# controller9.net
KiCad netlist of a schematic drawn in EAGLE
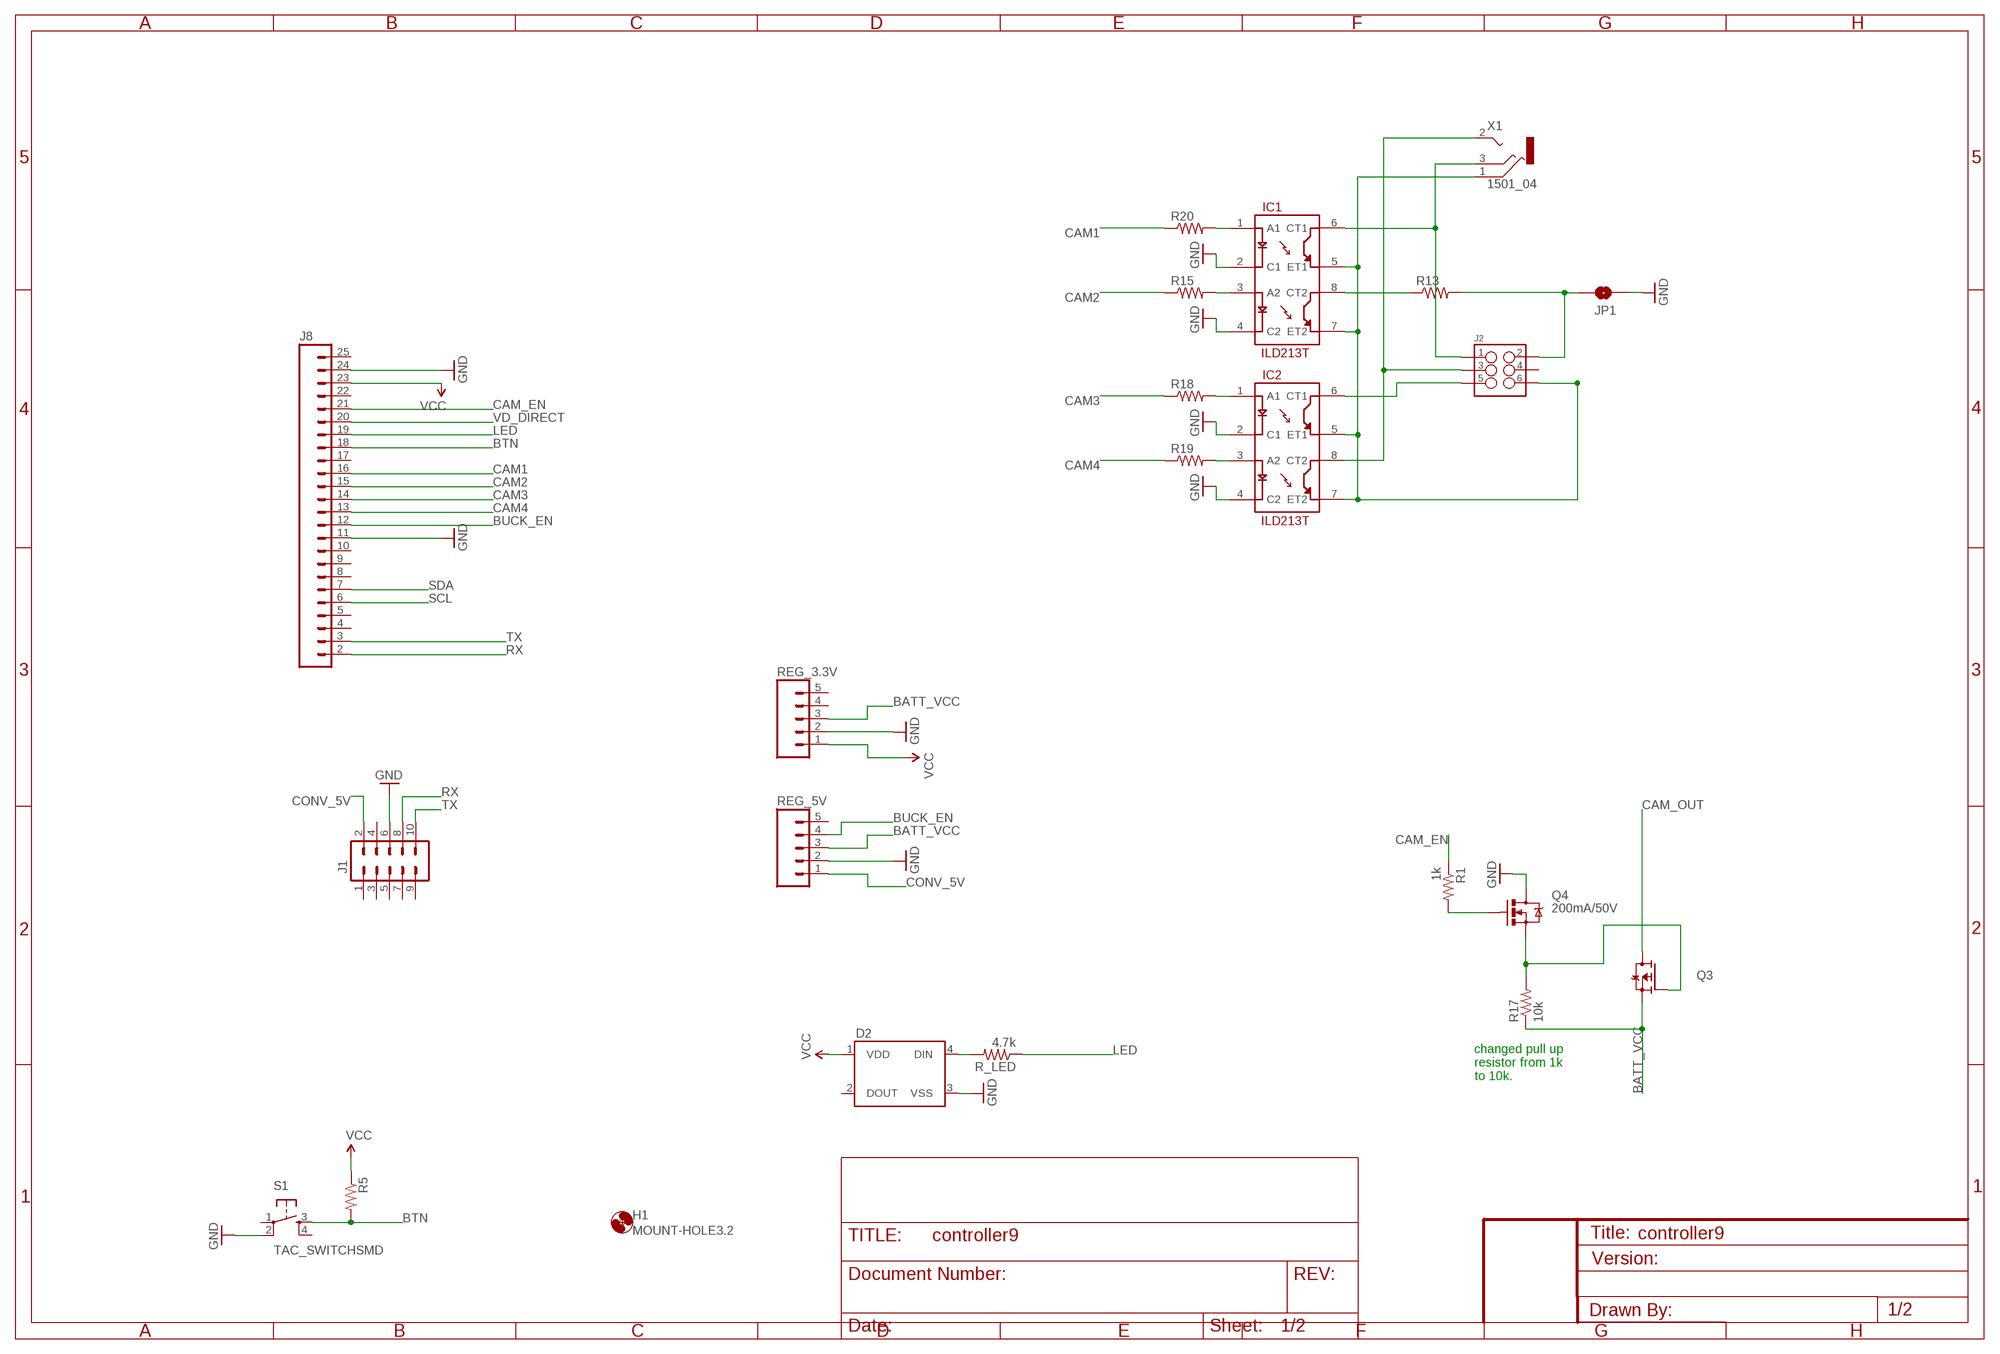
[diagram p0: schematic, sheet 1]
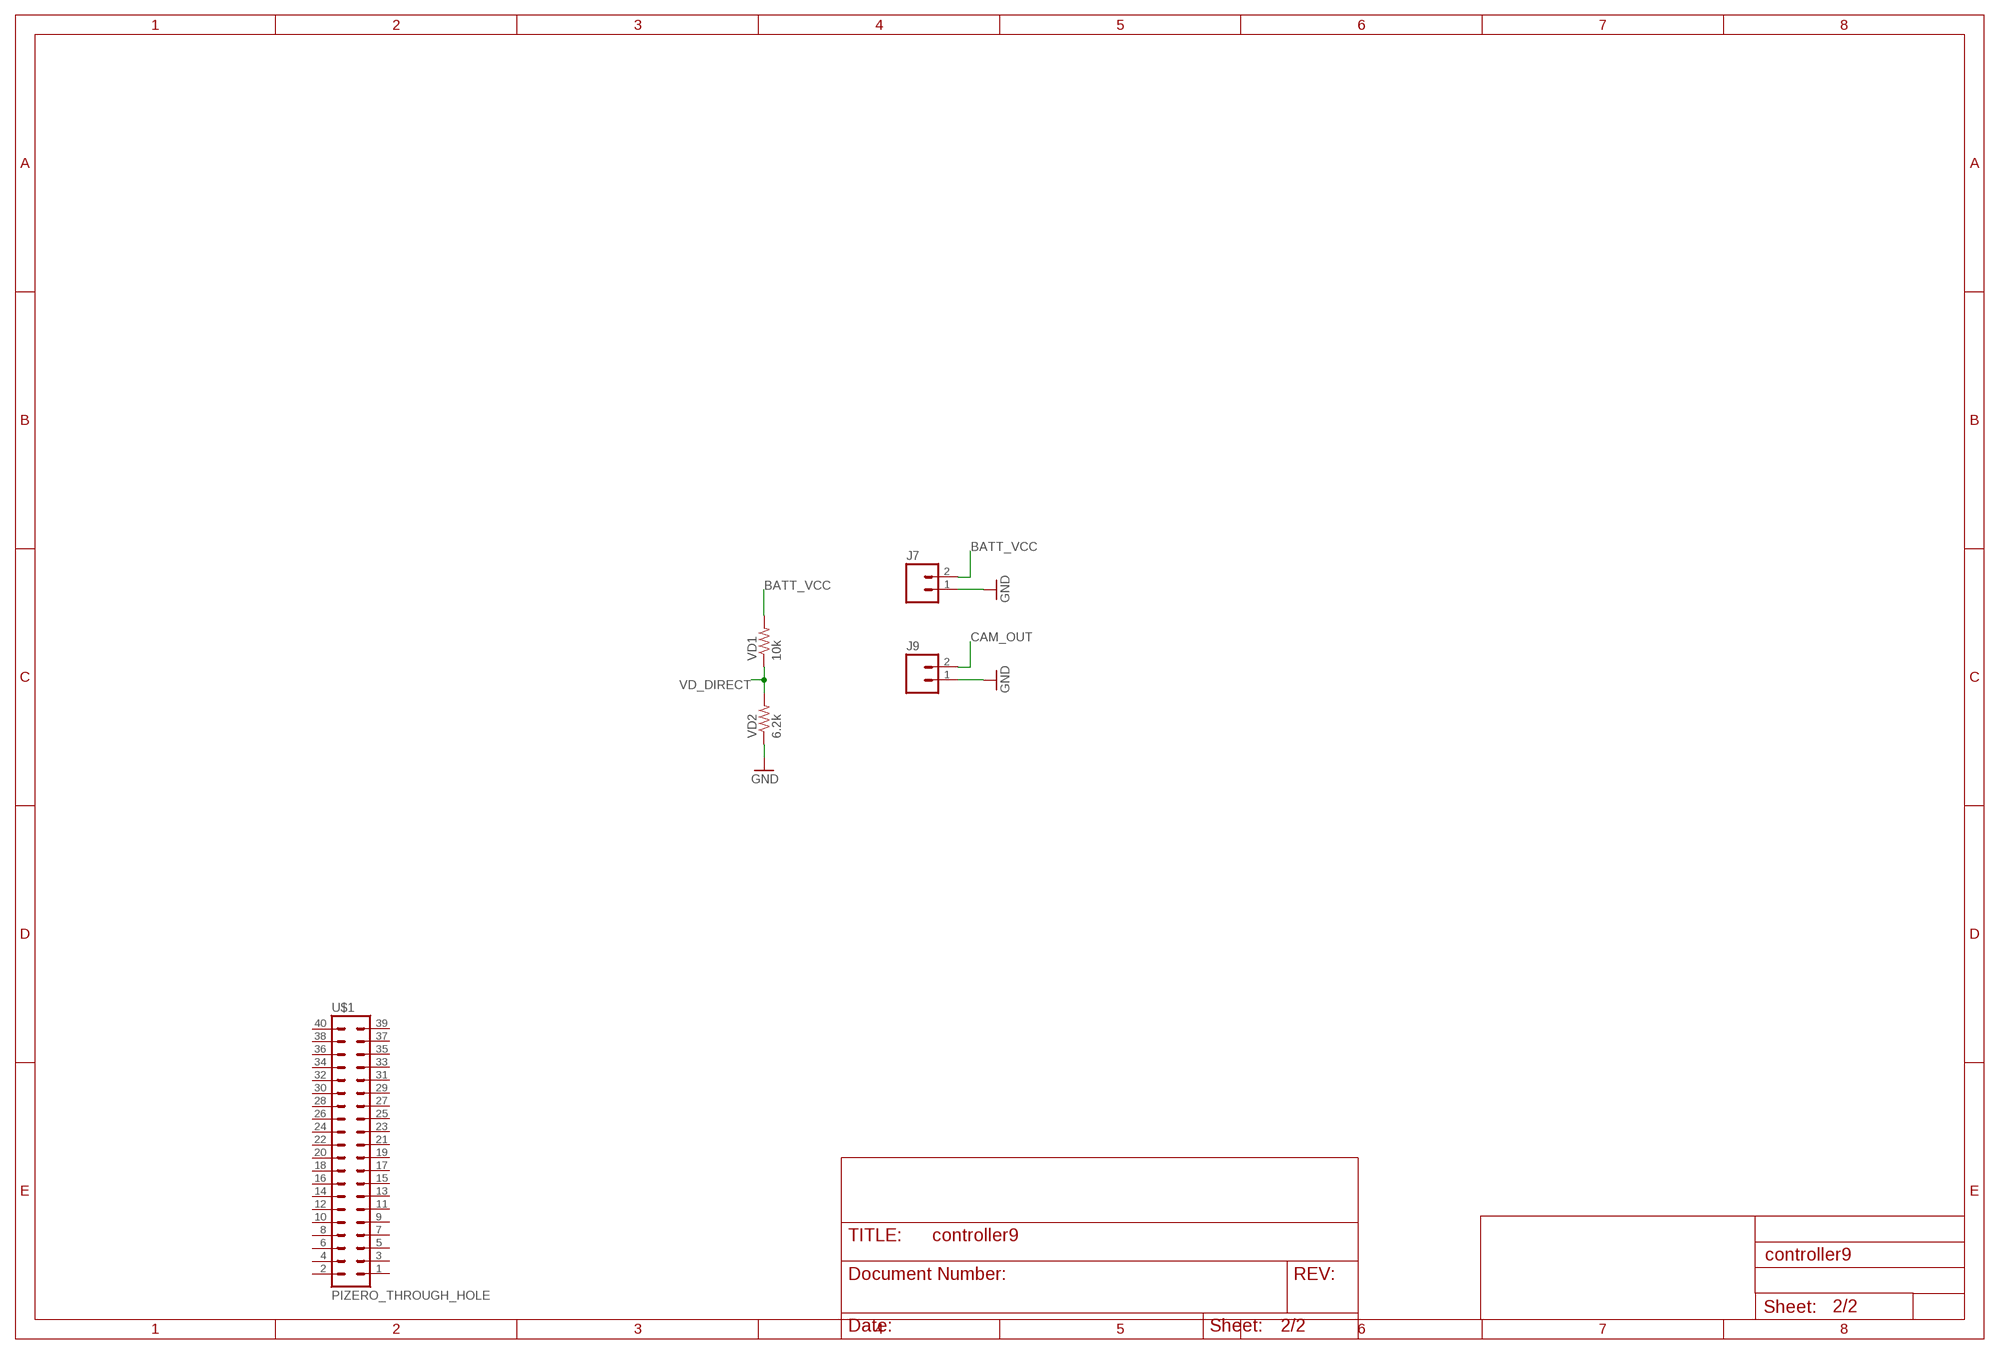
[diagram p1: schematic, sheet 2]

(export (version "E")
  (design (tool "Eeschema 10.0.6"))
  (components
    (comp (ref "J7")
      (value "M02LOCK")
      (footprint "eagle-import:1X02_LOCK")
      (libsource (lib "eagle-import") (part "M02LOCK"))
    )
    (comp (ref "J9")
      (value "M02LOCK")
      (footprint "eagle-import:1X02_LOCK")
      (libsource (lib "eagle-import") (part "M02LOCK"))
    )
    (comp (ref "U$1")
      (value "PIZERO_THROUGH_HOLE")
      (footprint "eagle-import:PIZERO_THOUGH_HOLE")
      (libsource (lib "eagle-import") (part "PIZERO_THROUGH_HOLE"))
    )
    (comp (ref "VD1")
      (value "10k")
      (footprint "eagle-import:0805")
      (libsource (lib "eagle-import") (part "RESISTOR0805-RES"))
    )
    (comp (ref "VD2")
      (value "6.2k")
      (footprint "eagle-import:0805")
      (libsource (lib "eagle-import") (part "RESISTOR0805-RES"))
    )
    (comp (ref "D2")
      (value "WS2812B")
      (footprint "eagle-import:WS2812B")
      (libsource (lib "eagle-import") (part "WS2812B"))
    )
    (comp (ref "H1")
      (value "MOUNT-HOLE3.2")
      (footprint "eagle-import:3,2")
      (libsource (lib "eagle-import") (part "MOUNT-HOLE3.2"))
    )
    (comp (ref "IC1")
      (value "ILD213T")
      (footprint "eagle-import:SO08")
      (libsource (lib "eagle-import") (part "ILD213T"))
    )
    (comp (ref "IC2")
      (value "ILD213T")
      (footprint "eagle-import:SO08")
      (libsource (lib "eagle-import") (part "ILD213T"))
    )
    (comp (ref "J1")
      (value "M05X2PTH")
      (footprint "eagle-import:AVR_ICSP")
      (libsource (lib "eagle-import") (part "M05X2PTH"))
    )
    (comp (ref "J2")
      (value "M03X2FEMALE")
      (footprint "eagle-import:2X3")
      (libsource (lib "eagle-import") (part "M03X2FEMALE"))
    )
    (comp (ref "J8")
      (value "M24LOCK")
      (footprint "eagle-import:1X24_LOCK")
      (libsource (lib "eagle-import") (part "M24LOCK"))
    )
    (comp (ref "JP1")
      (value "JUMPER-PAD-2-NOYES_SILK")
      (footprint "eagle-import:PAD-JUMPER-2-NO_YES_SILK")
      (libsource (lib "eagle-import") (part "JUMPER-PAD-2-NOYES_SILK"))
    )
    (comp (ref "Q3")
      (value "FDD4141TO252")
      (footprint "eagle-import:TO252")
      (libsource (lib "eagle-import") (part "FDD4141TO252"))
    )
    (comp (ref "Q4")
      (value "200mA/50V")
      (footprint "eagle-import:SOT23-3")
      (libsource (lib "eagle-import") (part "MOSFET-NCHANNELBSS138"))
    )
    (comp (ref "R1")
      (value "1k")
      (footprint "eagle-import:0805")
      (libsource (lib "eagle-import") (part "SparkFun-Resistors_RESISTOR0805-RES"))
    )
    (comp (ref "R5")
      (value "RESISTOR0805-RES")
      (footprint "eagle-import:0805")
      (libsource (lib "eagle-import") (part "RESISTOR0805-RES"))
    )
    (comp (ref "R13")
      (value "RESISTOR0805-RES")
      (footprint "eagle-import:0805")
      (libsource (lib "eagle-import") (part "RESISTOR0805-RES"))
    )
    (comp (ref "R15")
      (value "RESISTOR0805-RES")
      (footprint "eagle-import:0805")
      (libsource (lib "eagle-import") (part "RESISTOR0805-RES"))
    )
    (comp (ref "R17")
      (value "10k")
      (footprint "eagle-import:0805")
      (libsource (lib "eagle-import") (part "SparkFun-Resistors_RESISTOR0805-RES"))
    )
    (comp (ref "R18")
      (value "RESISTOR0805-RES")
      (footprint "eagle-import:0805")
      (libsource (lib "eagle-import") (part "RESISTOR0805-RES"))
    )
    (comp (ref "R19")
      (value "RESISTOR0805-RES")
      (footprint "eagle-import:0805")
      (libsource (lib "eagle-import") (part "RESISTOR0805-RES"))
    )
    (comp (ref "R20")
      (value "RESISTOR0805-RES")
      (footprint "eagle-import:0805")
      (libsource (lib "eagle-import") (part "RESISTOR0805-RES"))
    )
    (comp (ref "REG_3.3V")
      (value "M05LOCK")
      (footprint "eagle-import:1X05_LOCK")
      (libsource (lib "eagle-import") (part "M05LOCK"))
    )
    (comp (ref "REG_5V")
      (value "M05LOCK")
      (footprint "eagle-import:1X05_LOCK")
      (libsource (lib "eagle-import") (part "M05LOCK"))
    )
    (comp (ref "R_LED")
      (value "4.7k")
      (footprint "eagle-import:0805")
      (libsource (lib "eagle-import") (part "SparkFun-Resistors_RESISTOR0805-RES"))
    )
    (comp (ref "S1")
      (value "TAC_SWITCHSMD")
      (footprint "eagle-import:TACTILE-PTH")
      (libsource (lib "eagle-import") (part "TAC_SWITCHPTH"))
    )
    (comp (ref "X1")
      (value "1501_04")
      (footprint "eagle-import:1501_05")
      (libsource (lib "eagle-import") (part "1501_04"))
    )
  )
  (nets
    (net (code "1") (name "BATT_VCC") (class "Default")
      (node (ref "J7") (pin "2") (pinfunction "2_2") (pintype "passive"))
      (node (ref "Q3") (pin "2") (pinfunction "S_2") (pintype "passive"))
      (node (ref "R17") (pin "1") (pinfunction "1_1") (pintype "passive"))
      (node (ref "REG_3.3V") (pin "3") (pinfunction "3_3") (pintype "passive"))
      (node (ref "REG_5V") (pin "3") (pinfunction "3_3") (pintype "passive"))
      (node (ref "VD1") (pin "2") (pinfunction "2_2") (pintype "passive"))
    )
    (net (code "2") (name "BTN") (class "Default")
      (node (ref "J8") (pin "18") (pinfunction "18_18") (pintype "passive"))
      (node (ref "R5") (pin "2") (pinfunction "2_2") (pintype "passive"))
      (node (ref "S1") (pin "3") (pinfunction "3_3") (pintype "passive"))
    )
    (net (code "3") (name "BUCK_EN") (class "Default")
      (node (ref "J8") (pin "12") (pinfunction "12_12") (pintype "passive"))
      (node (ref "REG_5V") (pin "4") (pinfunction "4_4") (pintype "passive"))
    )
    (net (code "4") (name "CAM1") (class "Default")
      (node (ref "J8") (pin "16") (pinfunction "16_16") (pintype "passive"))
      (node (ref "R20") (pin "1") (pinfunction "1_1") (pintype "passive"))
    )
    (net (code "5") (name "CAM2") (class "Default")
      (node (ref "J8") (pin "15") (pinfunction "15_15") (pintype "passive"))
      (node (ref "R15") (pin "1") (pinfunction "1_1") (pintype "passive"))
    )
    (net (code "6") (name "CAM3") (class "Default")
      (node (ref "J8") (pin "14") (pinfunction "14_14") (pintype "passive"))
      (node (ref "R18") (pin "1") (pinfunction "1_1") (pintype "passive"))
    )
    (net (code "7") (name "CAM4") (class "Default")
      (node (ref "J8") (pin "13") (pinfunction "13_13") (pintype "passive"))
      (node (ref "R19") (pin "1") (pinfunction "1_1") (pintype "passive"))
    )
    (net (code "8") (name "CAM_EN") (class "Default")
      (node (ref "J8") (pin "21") (pinfunction "21_21") (pintype "passive"))
      (node (ref "R1") (pin "1") (pinfunction "1_1") (pintype "passive"))
    )
    (net (code "9") (name "CAM_OUT") (class "Default")
      (node (ref "J9") (pin "2") (pinfunction "2_2") (pintype "passive"))
      (node (ref "Q3") (pin "3") (pinfunction "D_3") (pintype "passive"))
    )
    (net (code "10") (name "CONV_5V") (class "Default")
      (node (ref "J1") (pin "2") (pinfunction "2_2") (pintype "passive"))
      (node (ref "REG_5V") (pin "1") (pinfunction "1_1") (pintype "passive"))
    )
    (net (code "11") (name "GND") (class "Default")
      (node (ref "D2") (pin "3") (pinfunction "VSS_3") (pintype "power_in"))
      (node (ref "IC1") (pin "2") (pinfunction "C1_2") (pintype "bidirectional"))
      (node (ref "IC1") (pin "4") (pinfunction "C2_4") (pintype "bidirectional"))
      (node (ref "IC2") (pin "2") (pinfunction "C1_2") (pintype "bidirectional"))
      (node (ref "IC2") (pin "4") (pinfunction "C2_4") (pintype "bidirectional"))
      (node (ref "J1") (pin "6") (pinfunction "6_6") (pintype "passive"))
      (node (ref "J7") (pin "1") (pinfunction "1_1") (pintype "passive"))
      (node (ref "J8") (pin "11") (pinfunction "11_11") (pintype "passive"))
      (node (ref "J8") (pin "24") (pinfunction "24_24") (pintype "passive"))
      (node (ref "J9") (pin "1") (pinfunction "1_1") (pintype "passive"))
      (node (ref "JP1") (pin "1") (pinfunction "1_1") (pintype "passive"))
      (node (ref "Q4") (pin "3") (pinfunction "D_3") (pintype "passive"))
      (node (ref "REG_3.3V") (pin "2") (pinfunction "2_2") (pintype "passive"))
      (node (ref "REG_5V") (pin "2") (pinfunction "2_2") (pintype "passive"))
      (node (ref "S1") (pin "2") (pinfunction "2_2") (pintype "passive"))
      (node (ref "VD2") (pin "1") (pinfunction "1_1") (pintype "passive"))
    )
    (net (code "12") (name "LED") (class "Default")
      (node (ref "J8") (pin "19") (pinfunction "19_19") (pintype "passive"))
      (node (ref "R_LED") (pin "1") (pinfunction "1_1") (pintype "passive"))
    )
    (net (code "13") (name "Net-(D2-DIN)") (class "Default")
      (node (ref "D2") (pin "4") (pinfunction "DIN_4") (pintype "input"))
      (node (ref "R_LED") (pin "2") (pinfunction "2_2") (pintype "passive"))
    )
    (net (code "14") (name "Net-(IC1-A1)") (class "Default")
      (node (ref "IC1") (pin "1") (pinfunction "A1_1") (pintype "bidirectional"))
      (node (ref "R20") (pin "2") (pinfunction "2_2") (pintype "passive"))
    )
    (net (code "15") (name "Net-(IC1-A2)") (class "Default")
      (node (ref "IC1") (pin "3") (pinfunction "A2_3") (pintype "bidirectional"))
      (node (ref "R15") (pin "2") (pinfunction "2_2") (pintype "passive"))
    )
    (net (code "16") (name "Net-(IC1-CT1)") (class "Default")
      (node (ref "IC1") (pin "6") (pinfunction "CT1_6") (pintype "bidirectional"))
      (node (ref "J2") (pin "1") (pinfunction "1_1") (pintype "bidirectional"))
      (node (ref "X1") (pin "3") (pinfunction "3_3") (pintype "passive"))
    )
    (net (code "17") (name "Net-(IC1-CT2)") (class "Default")
      (node (ref "IC1") (pin "8") (pinfunction "CT2_8") (pintype "bidirectional"))
      (node (ref "R13") (pin "1") (pinfunction "1_1") (pintype "passive"))
    )
    (net (code "18") (name "Net-(IC1-ET1)") (class "Default")
      (node (ref "IC1") (pin "5") (pinfunction "ET1_5") (pintype "bidirectional"))
      (node (ref "IC1") (pin "7") (pinfunction "ET2_7") (pintype "bidirectional"))
      (node (ref "IC2") (pin "5") (pinfunction "ET1_5") (pintype "bidirectional"))
      (node (ref "IC2") (pin "7") (pinfunction "ET2_7") (pintype "bidirectional"))
      (node (ref "J2") (pin "6") (pinfunction "6_6") (pintype "bidirectional"))
      (node (ref "X1") (pin "1") (pinfunction "1_1") (pintype "passive"))
    )
    (net (code "19") (name "Net-(IC2-A1)") (class "Default")
      (node (ref "IC2") (pin "1") (pinfunction "A1_1") (pintype "bidirectional"))
      (node (ref "R18") (pin "2") (pinfunction "2_2") (pintype "passive"))
    )
    (net (code "20") (name "Net-(IC2-A2)") (class "Default")
      (node (ref "IC2") (pin "3") (pinfunction "A2_3") (pintype "bidirectional"))
      (node (ref "R19") (pin "2") (pinfunction "2_2") (pintype "passive"))
    )
    (net (code "21") (name "Net-(IC2-CT1)") (class "Default")
      (node (ref "IC2") (pin "6") (pinfunction "CT1_6") (pintype "bidirectional"))
      (node (ref "J2") (pin "5") (pinfunction "5_5") (pintype "bidirectional"))
    )
    (net (code "22") (name "Net-(IC2-CT2)") (class "Default")
      (node (ref "IC2") (pin "8") (pinfunction "CT2_8") (pintype "bidirectional"))
      (node (ref "J2") (pin "3") (pinfunction "3_3") (pintype "bidirectional"))
      (node (ref "X1") (pin "2") (pinfunction "2_2") (pintype "passive"))
    )
    (net (code "23") (name "Net-(J2-Pad2)") (class "Default")
      (node (ref "J2") (pin "2") (pinfunction "2_2") (pintype "bidirectional"))
      (node (ref "JP1") (pin "2") (pinfunction "2_2") (pintype "passive"))
      (node (ref "R13") (pin "2") (pinfunction "2_2") (pintype "passive"))
    )
    (net (code "24") (name "Net-(Q3-G)") (class "Default")
      (node (ref "Q3") (pin "1") (pinfunction "G_1") (pintype "passive"))
      (node (ref "Q4") (pin "2") (pinfunction "S_2") (pintype "passive"))
      (node (ref "R17") (pin "2") (pinfunction "2_2") (pintype "passive"))
    )
    (net (code "25") (name "Net-(Q4-G)") (class "Default")
      (node (ref "Q4") (pin "1") (pinfunction "G_1") (pintype "passive"))
      (node (ref "R1") (pin "2") (pinfunction "2_2") (pintype "passive"))
    )
    (net (code "26") (name "RX") (class "Default")
      (node (ref "J1") (pin "8") (pinfunction "8_8") (pintype "passive"))
      (node (ref "J8") (pin "2") (pinfunction "2_2") (pintype "passive"))
    )
    (net (code "27") (name "SCL") (class "Default")
      (node (ref "J8") (pin "6") (pinfunction "6_6") (pintype "passive"))
    )
    (net (code "28") (name "SDA") (class "Default")
      (node (ref "J8") (pin "7") (pinfunction "7_7") (pintype "passive"))
    )
    (net (code "29") (name "TX") (class "Default")
      (node (ref "J1") (pin "10") (pinfunction "10_10") (pintype "passive"))
      (node (ref "J8") (pin "3") (pinfunction "3_3") (pintype "passive"))
    )
    (net (code "30") (name "VCC") (class "Default")
      (node (ref "D2") (pin "1") (pinfunction "VDD_1") (pintype "power_in"))
      (node (ref "J8") (pin "23") (pinfunction "23_23") (pintype "passive"))
      (node (ref "R5") (pin "1") (pinfunction "1_1") (pintype "passive"))
      (node (ref "REG_3.3V") (pin "1") (pinfunction "1_1") (pintype "passive"))
    )
    (net (code "31") (name "VD_DIRECT") (class "Default")
      (node (ref "J8") (pin "20") (pinfunction "20_20") (pintype "passive"))
      (node (ref "VD1") (pin "1") (pinfunction "1_1") (pintype "passive"))
      (node (ref "VD2") (pin "2") (pinfunction "2_2") (pintype "passive"))
    )
    (net (code "32") (name "unconnected-(D2-DOUT-Pad2)") (class "Default")
      (node (ref "D2") (pin "2") (pinfunction "DOUT_2") (pintype "output"))
    )
    (net (code "33") (name "unconnected-(J1-Pad1)") (class "Default")
      (node (ref "J1") (pin "1") (pinfunction "1_1") (pintype "passive"))
    )
    (net (code "34") (name "unconnected-(J1-Pad3)") (class "Default")
      (node (ref "J1") (pin "3") (pinfunction "3_3") (pintype "passive"))
    )
    (net (code "35") (name "unconnected-(J1-Pad4)") (class "Default")
      (node (ref "J1") (pin "4") (pinfunction "4_4") (pintype "passive"))
    )
    (net (code "36") (name "unconnected-(J1-Pad5)") (class "Default")
      (node (ref "J1") (pin "5") (pinfunction "5_5") (pintype "passive"))
    )
    (net (code "37") (name "unconnected-(J1-Pad7)") (class "Default")
      (node (ref "J1") (pin "7") (pinfunction "7_7") (pintype "passive"))
    )
    (net (code "38") (name "unconnected-(J1-Pad9)") (class "Default")
      (node (ref "J1") (pin "9") (pinfunction "9_9") (pintype "passive"))
    )
    (net (code "39") (name "unconnected-(J2-Pad4)") (class "Default")
      (node (ref "J2") (pin "4") (pinfunction "4_4") (pintype "bidirectional"))
    )
    (net (code "40") (name "unconnected-(J8-Pad4)") (class "Default")
      (node (ref "J8") (pin "4") (pinfunction "4_4") (pintype "passive"))
    )
    (net (code "41") (name "unconnected-(J8-Pad5)") (class "Default")
      (node (ref "J8") (pin "5") (pinfunction "5_5") (pintype "passive"))
    )
    (net (code "42") (name "unconnected-(J8-Pad8)") (class "Default")
      (node (ref "J8") (pin "8") (pinfunction "8_8") (pintype "passive"))
    )
    (net (code "43") (name "unconnected-(J8-Pad9)") (class "Default")
      (node (ref "J8") (pin "9") (pinfunction "9_9") (pintype "passive"))
    )
    (net (code "44") (name "unconnected-(J8-Pad10)") (class "Default")
      (node (ref "J8") (pin "10") (pinfunction "10_10") (pintype "passive"))
    )
    (net (code "45") (name "unconnected-(J8-Pad17)") (class "Default")
      (node (ref "J8") (pin "17") (pinfunction "17_17") (pintype "passive"))
    )
    (net (code "46") (name "unconnected-(J8-Pad22)") (class "Default")
      (node (ref "J8") (pin "22") (pinfunction "22_22") (pintype "passive"))
    )
    (net (code "47") (name "unconnected-(J8-Pad25)") (class "Default")
      (node (ref "J8") (pin "25") (pinfunction "25_25") (pintype "passive"))
    )
    (net (code "48") (name "unconnected-(REG_3.3V-Pad4)") (class "Default")
      (node (ref "REG_3.3V") (pin "4") (pinfunction "4_4") (pintype "passive"))
    )
    (net (code "49") (name "unconnected-(REG_3.3V-Pad5)") (class "Default")
      (node (ref "REG_3.3V") (pin "5") (pinfunction "5_5") (pintype "passive"))
    )
    (net (code "50") (name "unconnected-(REG_5V-Pad5)") (class "Default")
      (node (ref "REG_5V") (pin "5") (pinfunction "5_5") (pintype "passive"))
    )
    (net (code "51") (name "unconnected-(S1-Pad1)") (class "Default")
      (node (ref "S1") (pin "1") (pinfunction "1_1") (pintype "passive"))
    )
    (net (code "52") (name "unconnected-(S1-Pad4)") (class "Default")
      (node (ref "S1") (pin "4") (pinfunction "4_4") (pintype "passive"))
    )
    (net (code "53") (name "unconnected-(U$1-Pad1)") (class "Default")
      (node (ref "U$1") (pin "1") (pinfunction "1_1") (pintype "passive"))
    )
    (net (code "54") (name "unconnected-(U$1-Pad2)") (class "Default")
      (node (ref "U$1") (pin "2") (pinfunction "2_2") (pintype "passive"))
    )
    (net (code "55") (name "unconnected-(U$1-Pad3)") (class "Default")
      (node (ref "U$1") (pin "3") (pinfunction "3_3") (pintype "passive"))
    )
    (net (code "56") (name "unconnected-(U$1-Pad4)") (class "Default")
      (node (ref "U$1") (pin "4") (pinfunction "4_4") (pintype "passive"))
    )
    (net (code "57") (name "unconnected-(U$1-Pad5)") (class "Default")
      (node (ref "U$1") (pin "5") (pinfunction "5_5") (pintype "passive"))
    )
    (net (code "58") (name "unconnected-(U$1-Pad6)") (class "Default")
      (node (ref "U$1") (pin "6") (pinfunction "6_6") (pintype "passive"))
    )
    (net (code "59") (name "unconnected-(U$1-Pad7)") (class "Default")
      (node (ref "U$1") (pin "7") (pinfunction "7_7") (pintype "passive"))
    )
    (net (code "60") (name "unconnected-(U$1-Pad8)") (class "Default")
      (node (ref "U$1") (pin "8") (pinfunction "8_8") (pintype "passive"))
    )
    (net (code "61") (name "unconnected-(U$1-Pad9)") (class "Default")
      (node (ref "U$1") (pin "9") (pinfunction "9_9") (pintype "passive"))
    )
    (net (code "62") (name "unconnected-(U$1-Pad10)") (class "Default")
      (node (ref "U$1") (pin "10") (pinfunction "10_10") (pintype "passive"))
    )
    (net (code "63") (name "unconnected-(U$1-Pad11)") (class "Default")
      (node (ref "U$1") (pin "11") (pinfunction "11_11") (pintype "passive"))
    )
    (net (code "64") (name "unconnected-(U$1-Pad12)") (class "Default")
      (node (ref "U$1") (pin "12") (pinfunction "12_12") (pintype "passive"))
    )
    (net (code "65") (name "unconnected-(U$1-Pad13)") (class "Default")
      (node (ref "U$1") (pin "13") (pinfunction "13_13") (pintype "passive"))
    )
    (net (code "66") (name "unconnected-(U$1-Pad14)") (class "Default")
      (node (ref "U$1") (pin "14") (pinfunction "14_14") (pintype "passive"))
    )
    (net (code "67") (name "unconnected-(U$1-Pad15)") (class "Default")
      (node (ref "U$1") (pin "15") (pinfunction "15_15") (pintype "passive"))
    )
    (net (code "68") (name "unconnected-(U$1-Pad16)") (class "Default")
      (node (ref "U$1") (pin "16") (pinfunction "16_16") (pintype "passive"))
    )
    (net (code "69") (name "unconnected-(U$1-Pad17)") (class "Default")
      (node (ref "U$1") (pin "17") (pinfunction "17_17") (pintype "passive"))
    )
    (net (code "70") (name "unconnected-(U$1-Pad18)") (class "Default")
      (node (ref "U$1") (pin "18") (pinfunction "18_18") (pintype "passive"))
    )
    (net (code "71") (name "unconnected-(U$1-Pad19)") (class "Default")
      (node (ref "U$1") (pin "19") (pinfunction "19_19") (pintype "passive"))
    )
    (net (code "72") (name "unconnected-(U$1-Pad20)") (class "Default")
      (node (ref "U$1") (pin "20") (pinfunction "20_20") (pintype "passive"))
    )
    (net (code "73") (name "unconnected-(U$1-Pad21)") (class "Default")
      (node (ref "U$1") (pin "21") (pinfunction "21_21") (pintype "passive"))
    )
    (net (code "74") (name "unconnected-(U$1-Pad22)") (class "Default")
      (node (ref "U$1") (pin "22") (pinfunction "22_22") (pintype "passive"))
    )
    (net (code "75") (name "unconnected-(U$1-Pad23)") (class "Default")
      (node (ref "U$1") (pin "23") (pinfunction "23_23") (pintype "passive"))
    )
    (net (code "76") (name "unconnected-(U$1-Pad24)") (class "Default")
      (node (ref "U$1") (pin "24") (pinfunction "24_24") (pintype "passive"))
    )
    (net (code "77") (name "unconnected-(U$1-Pad25)") (class "Default")
      (node (ref "U$1") (pin "25") (pinfunction "25_25") (pintype "passive"))
    )
    (net (code "78") (name "unconnected-(U$1-Pad26)") (class "Default")
      (node (ref "U$1") (pin "26") (pinfunction "26_26") (pintype "passive"))
    )
    (net (code "79") (name "unconnected-(U$1-Pad27)") (class "Default")
      (node (ref "U$1") (pin "27") (pinfunction "27_27") (pintype "passive"))
    )
    (net (code "80") (name "unconnected-(U$1-Pad28)") (class "Default")
      (node (ref "U$1") (pin "28") (pinfunction "28_28") (pintype "passive"))
    )
    (net (code "81") (name "unconnected-(U$1-Pad29)") (class "Default")
      (node (ref "U$1") (pin "29") (pinfunction "29_29") (pintype "passive"))
    )
    (net (code "82") (name "unconnected-(U$1-Pad30)") (class "Default")
      (node (ref "U$1") (pin "30") (pinfunction "30_30") (pintype "passive"))
    )
    (net (code "83") (name "unconnected-(U$1-Pad31)") (class "Default")
      (node (ref "U$1") (pin "31") (pinfunction "31_31") (pintype "passive"))
    )
    (net (code "84") (name "unconnected-(U$1-Pad32)") (class "Default")
      (node (ref "U$1") (pin "32") (pinfunction "32_32") (pintype "passive"))
    )
    (net (code "85") (name "unconnected-(U$1-Pad33)") (class "Default")
      (node (ref "U$1") (pin "33") (pinfunction "33_33") (pintype "passive"))
    )
    (net (code "86") (name "unconnected-(U$1-Pad34)") (class "Default")
      (node (ref "U$1") (pin "34") (pinfunction "34_34") (pintype "passive"))
    )
    (net (code "87") (name "unconnected-(U$1-Pad35)") (class "Default")
      (node (ref "U$1") (pin "35") (pinfunction "35_35") (pintype "passive"))
    )
    (net (code "88") (name "unconnected-(U$1-Pad36)") (class "Default")
      (node (ref "U$1") (pin "36") (pinfunction "36_36") (pintype "passive"))
    )
    (net (code "89") (name "unconnected-(U$1-Pad37)") (class "Default")
      (node (ref "U$1") (pin "37") (pinfunction "37_37") (pintype "passive"))
    )
    (net (code "90") (name "unconnected-(U$1-Pad38)") (class "Default")
      (node (ref "U$1") (pin "38") (pinfunction "38_38") (pintype "passive"))
    )
    (net (code "91") (name "unconnected-(U$1-Pad39)") (class "Default")
      (node (ref "U$1") (pin "39") (pinfunction "39_39") (pintype "passive"))
    )
    (net (code "92") (name "unconnected-(U$1-Pad40)") (class "Default")
      (node (ref "U$1") (pin "40") (pinfunction "40_40") (pintype "passive"))
    )
  )
)
